# Braille_V1.net
KiCad netlist of a schematic drawn in EAGLE
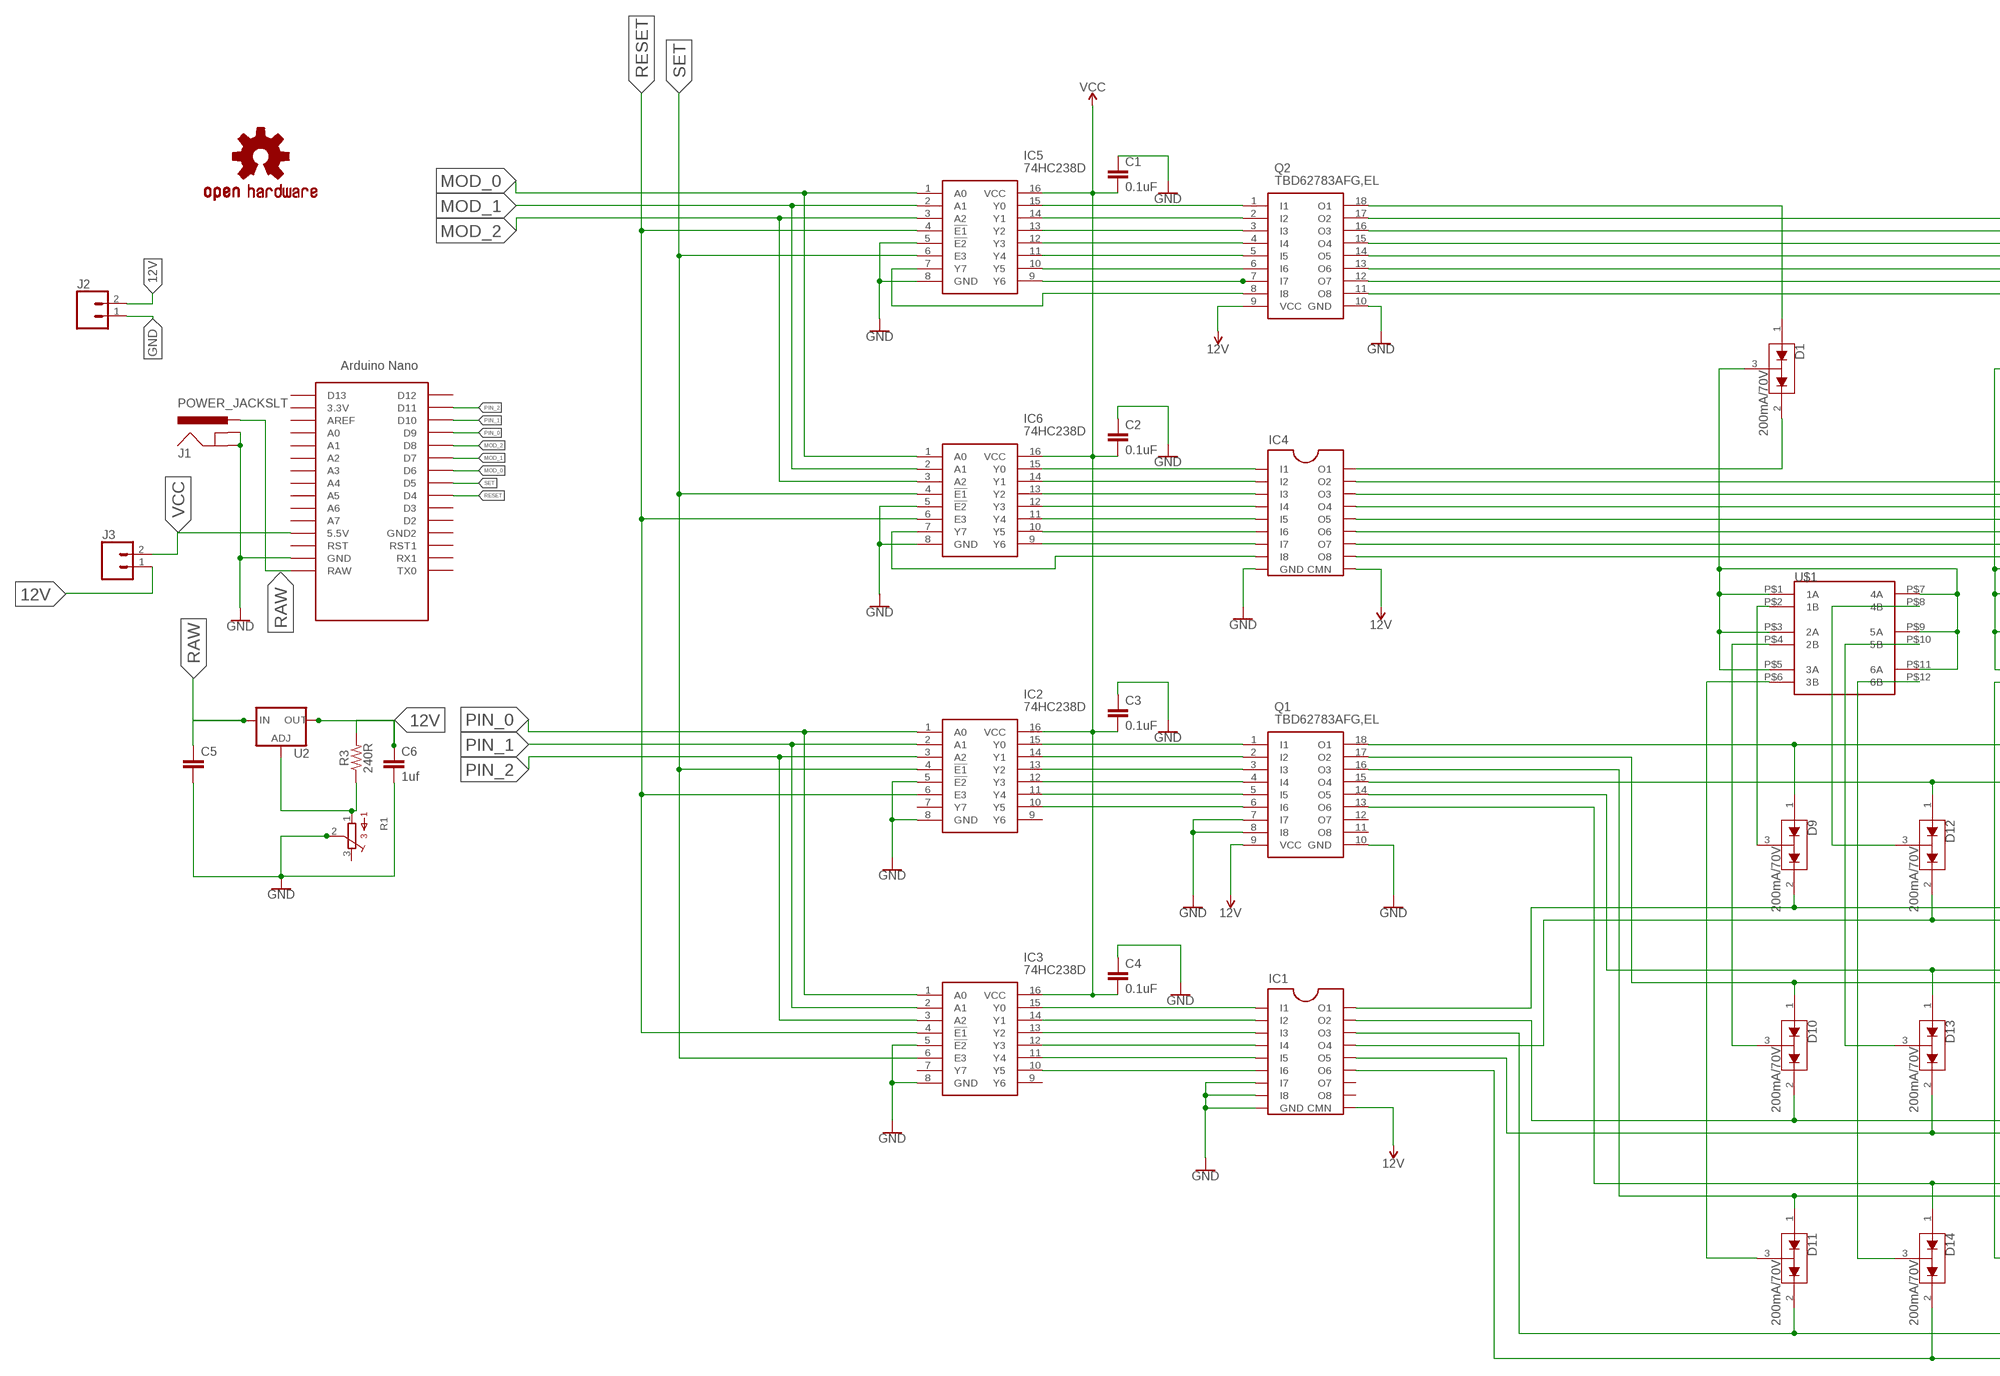
[diagram p0: schematic, sheet 1, part 1 of 2]
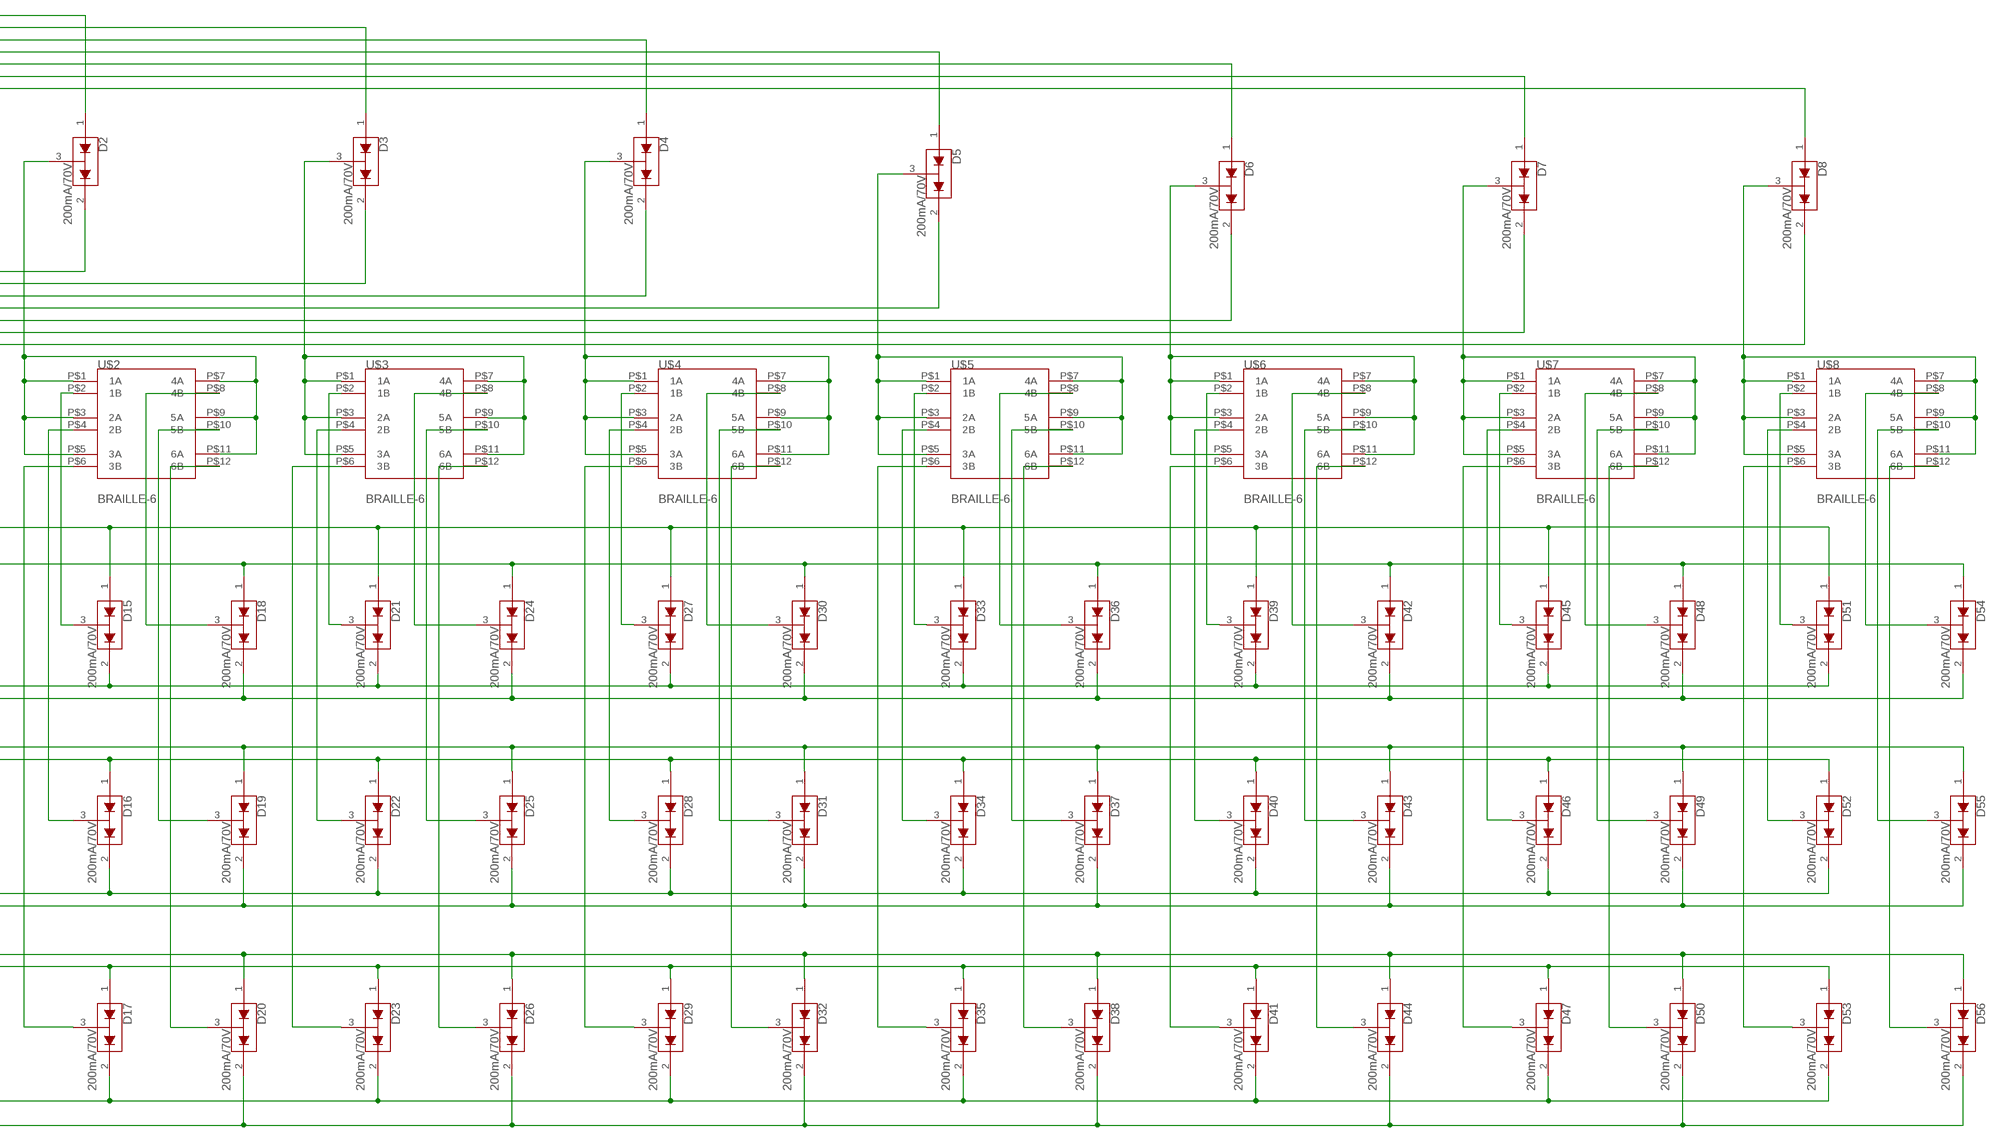
[diagram p1: schematic, sheet 1, part 2 of 2]

(export (version "E")
  (design (tool "Eeschema 10.0.6"))
  (components
    (comp (ref "C1")
      (value "0.1uF")
      (footprint "eagle-import:0603")
      (libsource (lib "eagle-import") (part "0.1UF-0603-25V-(+80/-20%)"))
    )
    (comp (ref "C2")
      (value "0.1uF")
      (footprint "eagle-import:0603")
      (libsource (lib "eagle-import") (part "0.1UF-0603-25V-(+80/-20%)"))
    )
    (comp (ref "C3")
      (value "0.1uF")
      (footprint "eagle-import:0603")
      (libsource (lib "eagle-import") (part "0.1UF-0603-25V-(+80/-20%)"))
    )
    (comp (ref "C4")
      (value "0.1uF")
      (footprint "eagle-import:0603")
      (libsource (lib "eagle-import") (part "0.1UF-0603-25V-(+80/-20%)"))
    )
    (comp (ref "C5")
      (value "0.1uF")
      (footprint "eagle-import:0603")
      (libsource (lib "eagle-import") (part "9.0PF-0603-50V-10%"))
    )
    (comp (ref "C6")
      (value "1uf")
      (footprint "eagle-import:0603")
      (libsource (lib "eagle-import") (part "9.0PF-0603-50V-10%"))
    )
    (comp (ref "D1")
      (value "200mA/70V")
      (footprint "eagle-import:SOT23-3")
      (libsource (lib "eagle-import") (part "BAV99"))
    )
    (comp (ref "D2")
      (value "200mA/70V")
      (footprint "eagle-import:SOT23-3")
      (libsource (lib "eagle-import") (part "BAV99"))
    )
    (comp (ref "D3")
      (value "200mA/70V")
      (footprint "eagle-import:SOT23-3")
      (libsource (lib "eagle-import") (part "BAV99"))
    )
    (comp (ref "D4")
      (value "200mA/70V")
      (footprint "eagle-import:SOT23-3")
      (libsource (lib "eagle-import") (part "BAV99"))
    )
    (comp (ref "D5")
      (value "200mA/70V")
      (footprint "eagle-import:SOT23-3")
      (libsource (lib "eagle-import") (part "BAV99"))
    )
    (comp (ref "D6")
      (value "200mA/70V")
      (footprint "eagle-import:SOT23-3")
      (libsource (lib "eagle-import") (part "BAV99"))
    )
    (comp (ref "D7")
      (value "200mA/70V")
      (footprint "eagle-import:SOT23-3")
      (libsource (lib "eagle-import") (part "BAV99"))
    )
    (comp (ref "D8")
      (value "200mA/70V")
      (footprint "eagle-import:SOT23-3")
      (libsource (lib "eagle-import") (part "BAV99"))
    )
    (comp (ref "D9")
      (value "200mA/70V")
      (footprint "eagle-import:SOT23-3")
      (libsource (lib "eagle-import") (part "BAV99"))
    )
    (comp (ref "D10")
      (value "200mA/70V")
      (footprint "eagle-import:SOT23-3")
      (libsource (lib "eagle-import") (part "BAV99"))
    )
    (comp (ref "D11")
      (value "200mA/70V")
      (footprint "eagle-import:SOT23-3")
      (libsource (lib "eagle-import") (part "BAV99"))
    )
    (comp (ref "D12")
      (value "200mA/70V")
      (footprint "eagle-import:SOT23-3")
      (libsource (lib "eagle-import") (part "BAV99"))
    )
    (comp (ref "D13")
      (value "200mA/70V")
      (footprint "eagle-import:SOT23-3")
      (libsource (lib "eagle-import") (part "BAV99"))
    )
    (comp (ref "D14")
      (value "200mA/70V")
      (footprint "eagle-import:SOT23-3")
      (libsource (lib "eagle-import") (part "BAV99"))
    )
    (comp (ref "D15")
      (value "200mA/70V")
      (footprint "eagle-import:SOT23-3")
      (libsource (lib "eagle-import") (part "BAV99"))
    )
    (comp (ref "D16")
      (value "200mA/70V")
      (footprint "eagle-import:SOT23-3")
      (libsource (lib "eagle-import") (part "BAV99"))
    )
    (comp (ref "D17")
      (value "200mA/70V")
      (footprint "eagle-import:SOT23-3")
      (libsource (lib "eagle-import") (part "BAV99"))
    )
    (comp (ref "D18")
      (value "200mA/70V")
      (footprint "eagle-import:SOT23-3")
      (libsource (lib "eagle-import") (part "BAV99"))
    )
    (comp (ref "D19")
      (value "200mA/70V")
      (footprint "eagle-import:SOT23-3")
      (libsource (lib "eagle-import") (part "BAV99"))
    )
    (comp (ref "D20")
      (value "200mA/70V")
      (footprint "eagle-import:SOT23-3")
      (libsource (lib "eagle-import") (part "BAV99"))
    )
    (comp (ref "D21")
      (value "200mA/70V")
      (footprint "eagle-import:SOT23-3")
      (libsource (lib "eagle-import") (part "BAV99"))
    )
    (comp (ref "D22")
      (value "200mA/70V")
      (footprint "eagle-import:SOT23-3")
      (libsource (lib "eagle-import") (part "BAV99"))
    )
    (comp (ref "D23")
      (value "200mA/70V")
      (footprint "eagle-import:SOT23-3")
      (libsource (lib "eagle-import") (part "BAV99"))
    )
    (comp (ref "D24")
      (value "200mA/70V")
      (footprint "eagle-import:SOT23-3")
      (libsource (lib "eagle-import") (part "BAV99"))
    )
    (comp (ref "D25")
      (value "200mA/70V")
      (footprint "eagle-import:SOT23-3")
      (libsource (lib "eagle-import") (part "BAV99"))
    )
    (comp (ref "D26")
      (value "200mA/70V")
      (footprint "eagle-import:SOT23-3")
      (libsource (lib "eagle-import") (part "BAV99"))
    )
    (comp (ref "D27")
      (value "200mA/70V")
      (footprint "eagle-import:SOT23-3")
      (libsource (lib "eagle-import") (part "BAV99"))
    )
    (comp (ref "D28")
      (value "200mA/70V")
      (footprint "eagle-import:SOT23-3")
      (libsource (lib "eagle-import") (part "BAV99"))
    )
    (comp (ref "D29")
      (value "200mA/70V")
      (footprint "eagle-import:SOT23-3")
      (libsource (lib "eagle-import") (part "BAV99"))
    )
    (comp (ref "D30")
      (value "200mA/70V")
      (footprint "eagle-import:SOT23-3")
      (libsource (lib "eagle-import") (part "BAV99"))
    )
    (comp (ref "D31")
      (value "200mA/70V")
      (footprint "eagle-import:SOT23-3")
      (libsource (lib "eagle-import") (part "BAV99"))
    )
    (comp (ref "D32")
      (value "200mA/70V")
      (footprint "eagle-import:SOT23-3")
      (libsource (lib "eagle-import") (part "BAV99"))
    )
    (comp (ref "D33")
      (value "200mA/70V")
      (footprint "eagle-import:SOT23-3")
      (libsource (lib "eagle-import") (part "BAV99"))
    )
    (comp (ref "D34")
      (value "200mA/70V")
      (footprint "eagle-import:SOT23-3")
      (libsource (lib "eagle-import") (part "BAV99"))
    )
    (comp (ref "D35")
      (value "200mA/70V")
      (footprint "eagle-import:SOT23-3")
      (libsource (lib "eagle-import") (part "BAV99"))
    )
    (comp (ref "D36")
      (value "200mA/70V")
      (footprint "eagle-import:SOT23-3")
      (libsource (lib "eagle-import") (part "BAV99"))
    )
    (comp (ref "D37")
      (value "200mA/70V")
      (footprint "eagle-import:SOT23-3")
      (libsource (lib "eagle-import") (part "BAV99"))
    )
    (comp (ref "D38")
      (value "200mA/70V")
      (footprint "eagle-import:SOT23-3")
      (libsource (lib "eagle-import") (part "BAV99"))
    )
    (comp (ref "D39")
      (value "200mA/70V")
      (footprint "eagle-import:SOT23-3")
      (libsource (lib "eagle-import") (part "BAV99"))
    )
    (comp (ref "D40")
      (value "200mA/70V")
      (footprint "eagle-import:SOT23-3")
      (libsource (lib "eagle-import") (part "BAV99"))
    )
    (comp (ref "D41")
      (value "200mA/70V")
      (footprint "eagle-import:SOT23-3")
      (libsource (lib "eagle-import") (part "BAV99"))
    )
    (comp (ref "D42")
      (value "200mA/70V")
      (footprint "eagle-import:SOT23-3")
      (libsource (lib "eagle-import") (part "BAV99"))
    )
    (comp (ref "D43")
      (value "200mA/70V")
      (footprint "eagle-import:SOT23-3")
      (libsource (lib "eagle-import") (part "BAV99"))
    )
    (comp (ref "D44")
      (value "200mA/70V")
      (footprint "eagle-import:SOT23-3")
      (libsource (lib "eagle-import") (part "BAV99"))
    )
    (comp (ref "D45")
      (value "200mA/70V")
      (footprint "eagle-import:SOT23-3")
      (libsource (lib "eagle-import") (part "BAV99"))
    )
    (comp (ref "D46")
      (value "200mA/70V")
      (footprint "eagle-import:SOT23-3")
      (libsource (lib "eagle-import") (part "BAV99"))
    )
    (comp (ref "D47")
      (value "200mA/70V")
      (footprint "eagle-import:SOT23-3")
      (libsource (lib "eagle-import") (part "BAV99"))
    )
    (comp (ref "D48")
      (value "200mA/70V")
      (footprint "eagle-import:SOT23-3")
      (libsource (lib "eagle-import") (part "BAV99"))
    )
    (comp (ref "D49")
      (value "200mA/70V")
      (footprint "eagle-import:SOT23-3")
      (libsource (lib "eagle-import") (part "BAV99"))
    )
    (comp (ref "D50")
      (value "200mA/70V")
      (footprint "eagle-import:SOT23-3")
      (libsource (lib "eagle-import") (part "BAV99"))
    )
    (comp (ref "D51")
      (value "200mA/70V")
      (footprint "eagle-import:SOT23-3")
      (libsource (lib "eagle-import") (part "BAV99"))
    )
    (comp (ref "D52")
      (value "200mA/70V")
      (footprint "eagle-import:SOT23-3")
      (libsource (lib "eagle-import") (part "BAV99"))
    )
    (comp (ref "D53")
      (value "200mA/70V")
      (footprint "eagle-import:SOT23-3")
      (libsource (lib "eagle-import") (part "BAV99"))
    )
    (comp (ref "D54")
      (value "200mA/70V")
      (footprint "eagle-import:SOT23-3")
      (libsource (lib "eagle-import") (part "BAV99"))
    )
    (comp (ref "D55")
      (value "200mA/70V")
      (footprint "eagle-import:SOT23-3")
      (libsource (lib "eagle-import") (part "BAV99"))
    )
    (comp (ref "D56")
      (value "200mA/70V")
      (footprint "eagle-import:SOT23-3")
      (libsource (lib "eagle-import") (part "BAV99"))
    )
    (comp (ref "IC1")
      (value "TD62083")
      (footprint "eagle-import:SO18")
      (libsource (lib "eagle-import") (part "TD62083"))
    )
    (comp (ref "IC2")
      (value "74HC238D")
      (footprint "eagle-import:SOIC127P600X175-16N")
      (fields (field (name "MOUSER_PART_NUMBER") "771-74HC238D"))
      (libsource (lib "eagle-import") (part "74HC238D"))
    )
    (comp (ref "IC3")
      (value "74HC238D")
      (footprint "eagle-import:SOIC127P600X175-16N")
      (fields (field (name "MOUSER_PART_NUMBER") "771-74HC238D"))
      (libsource (lib "eagle-import") (part "74HC238D"))
    )
    (comp (ref "IC4")
      (value "TD62083")
      (footprint "eagle-import:SO18")
      (libsource (lib "eagle-import") (part "TD62083"))
    )
    (comp (ref "IC5")
      (value "74HC238D")
      (footprint "eagle-import:SOIC127P600X175-16N")
      (fields (field (name "MOUSER_PART_NUMBER") "771-74HC238D"))
      (libsource (lib "eagle-import") (part "74HC238D"))
    )
    (comp (ref "IC6")
      (value "74HC238D")
      (footprint "eagle-import:SOIC127P600X175-16N")
      (fields (field (name "MOUSER_PART_NUMBER") "771-74HC238D"))
      (libsource (lib "eagle-import") (part "74HC238D"))
    )
    (comp (ref "J1")
      (value "POWER_JACKSLT")
      (footprint "eagle-import:POWER_JACK_SLOT")
      (libsource (lib "eagle-import") (part "POWER_JACKSLT"))
    )
    (comp (ref "J2")
      (value "CONN_02")
      (footprint "eagle-import:1X02")
      (libsource (lib "eagle-import") (part "CONN_02"))
    )
    (comp (ref "J3")
      (value "CONN_02")
      (footprint "eagle-import:1X02")
      (libsource (lib "eagle-import") (part "CONN_02"))
    )
    (comp (ref "LOGO1")
      (value "OSHW-LOGOL-COPPER")
      (footprint "eagle-import:OSHW-LOGO-L_COPPER")
      (libsource (lib "eagle-import") (part "OSHW-LOGOL-COPPER"))
    )
    (comp (ref "Q1")
      (value "TBD62783AFG,EL")
      (footprint "eagle-import:SOIC127P1030X245-18N")
      (fields (field (name "MOUSER_PART_NUMBER") "757-TBD62783AFGEL"))
      (libsource (lib "eagle-import") (part "TBD62783AFG,EL"))
    )
    (comp (ref "Q2")
      (value "TBD62783AFG,EL")
      (footprint "eagle-import:SOIC127P1030X245-18N")
      (fields (field (name "MOUSER_PART_NUMBER") "757-TBD62783AFGEL"))
      (libsource (lib "eagle-import") (part "TBD62783AFG,EL"))
    )
    (comp (ref "R1")
      (value "3362P")
      (footprint "eagle-import:3362P")
      (libsource (lib "eagle-import") (part "3362P"))
    )
    (comp (ref "R3")
      (value "240R")
      (footprint "eagle-import:0603")
      (libsource (lib "eagle-import") (part "RESISTOR0603"))
    )
    (comp (ref "U$1")
      (value "BRAILLE-6")
      (footprint "eagle-import:BRAILLE-6")
      (libsource (lib "eagle-import") (part "BRAILLE-6"))
    )
    (comp (ref "U$2")
      (value "BRAILLE-6")
      (footprint "eagle-import:BRAILLE-6")
      (libsource (lib "eagle-import") (part "BRAILLE-6"))
    )
    (comp (ref "U$3")
      (value "BRAILLE-6")
      (footprint "eagle-import:BRAILLE-6")
      (libsource (lib "eagle-import") (part "BRAILLE-6"))
    )
    (comp (ref "U$4")
      (value "BRAILLE-6")
      (footprint "eagle-import:BRAILLE-6")
      (libsource (lib "eagle-import") (part "BRAILLE-6"))
    )
    (comp (ref "U$5")
      (value "BRAILLE-6")
      (footprint "eagle-import:BRAILLE-6")
      (libsource (lib "eagle-import") (part "BRAILLE-6"))
    )
    (comp (ref "U$6")
      (value "BRAILLE-6")
      (footprint "eagle-import:BRAILLE-6")
      (libsource (lib "eagle-import") (part "BRAILLE-6"))
    )
    (comp (ref "U$7")
      (value "BRAILLE-6")
      (footprint "eagle-import:BRAILLE-6")
      (libsource (lib "eagle-import") (part "BRAILLE-6"))
    )
    (comp (ref "U$8")
      (value "BRAILLE-6")
      (footprint "eagle-import:BRAILLE-6")
      (libsource (lib "eagle-import") (part "BRAILLE-6"))
    )
    (comp (ref "U$9")
      (value "NANO")
      (footprint "eagle-import:NANO")
      (libsource (lib "eagle-import") (part "NANO"))
    )
    (comp (ref "U2")
      (value "LM317")
      (footprint "eagle-import:SOT223")
      (libsource (lib "eagle-import") (part "V_REG_317SMD"))
    )
  )
  (nets
    (net (code "1") (name "12V") (class "Default")
      (node (ref "C6") (pin "1") (pinfunction "1_1") (pintype "passive"))
      (node (ref "IC1") (pin "10") (pinfunction "CMN_10") (pintype "passive"))
      (node (ref "IC4") (pin "10") (pinfunction "CMN_10") (pintype "passive"))
      (node (ref "J2") (pin "2") (pinfunction "2_2") (pintype "passive"))
      (node (ref "J3") (pin "1") (pinfunction "1_1") (pintype "passive"))
      (node (ref "Q1") (pin "9") (pinfunction "VCC_9") (pintype "power_in"))
      (node (ref "Q2") (pin "9") (pinfunction "VCC_9") (pintype "power_in"))
      (node (ref "R3") (pin "2") (pinfunction "2_2") (pintype "passive"))
      (node (ref "U2") (pin "2") (pinfunction "OUT_2") (pintype "output"))
    )
    (net (code "2") (name "GND") (class "Default")
      (node (ref "C1") (pin "1") (pinfunction "1_1") (pintype "passive"))
      (node (ref "C2") (pin "1") (pinfunction "1_1") (pintype "passive"))
      (node (ref "C3") (pin "1") (pinfunction "1_1") (pintype "passive"))
      (node (ref "C4") (pin "1") (pinfunction "1_1") (pintype "passive"))
      (node (ref "C5") (pin "2") (pinfunction "2_2") (pintype "passive"))
      (node (ref "C6") (pin "2") (pinfunction "2_2") (pintype "passive"))
      (node (ref "IC1") (pin "7") (pinfunction "I7_7") (pintype "passive"))
      (node (ref "IC1") (pin "8") (pinfunction "I8_8") (pintype "passive"))
      (node (ref "IC1") (pin "9") (pinfunction "GND_9") (pintype "passive"))
      (node (ref "IC2") (pin "5") (pinfunction "~{E2}_5") (pintype "bidirectional"))
      (node (ref "IC2") (pin "8") (pinfunction "GND_8") (pintype "bidirectional"))
      (node (ref "IC3") (pin "5") (pinfunction "~{E2}_5") (pintype "bidirectional"))
      (node (ref "IC3") (pin "8") (pinfunction "GND_8") (pintype "bidirectional"))
      (node (ref "IC4") (pin "9") (pinfunction "GND_9") (pintype "passive"))
      (node (ref "IC5") (pin "5") (pinfunction "~{E2}_5") (pintype "bidirectional"))
      (node (ref "IC5") (pin "8") (pinfunction "GND_8") (pintype "bidirectional"))
      (node (ref "IC6") (pin "5") (pinfunction "~{E2}_5") (pintype "bidirectional"))
      (node (ref "IC6") (pin "8") (pinfunction "GND_8") (pintype "bidirectional"))
      (node (ref "J1") (pin "GND@1") (pinfunction "GNDBREAK_GND@1") (pintype "bidirectional"))
      (node (ref "J1") (pin "GND@2") (pinfunction "GND_GND@2") (pintype "bidirectional"))
      (node (ref "J2") (pin "1") (pinfunction "1_1") (pintype "passive"))
      (node (ref "Q1") (pin "10") (pinfunction "GND_10") (pintype "power_in"))
      (node (ref "Q1") (pin "7") (pinfunction "I7_7") (pintype "input"))
      (node (ref "Q1") (pin "8") (pinfunction "I8_8") (pintype "input"))
      (node (ref "Q2") (pin "10") (pinfunction "GND_10") (pintype "power_in"))
      (node (ref "R1") (pin "2") (pinfunction "2_2") (pintype "passive"))
      (node (ref "U$9") (pin "GND") (pinfunction "GND_GND") (pintype "bidirectional"))
    )
    (net (code "3") (name "MOD_0") (class "Default")
      (node (ref "IC5") (pin "1") (pinfunction "A0_1") (pintype "bidirectional"))
      (node (ref "IC6") (pin "1") (pinfunction "A0_1") (pintype "bidirectional"))
      (node (ref "U$9") (pin "D6") (pinfunction "D6_D6") (pintype "bidirectional"))
    )
    (net (code "4") (name "MOD_1") (class "Default")
      (node (ref "IC5") (pin "2") (pinfunction "A1_2") (pintype "bidirectional"))
      (node (ref "IC6") (pin "2") (pinfunction "A1_2") (pintype "bidirectional"))
      (node (ref "U$9") (pin "D7") (pinfunction "D7_D7") (pintype "bidirectional"))
    )
    (net (code "5") (name "MOD_2") (class "Default")
      (node (ref "IC5") (pin "3") (pinfunction "A2_3") (pintype "bidirectional"))
      (node (ref "IC6") (pin "3") (pinfunction "A2_3") (pintype "bidirectional"))
      (node (ref "U$9") (pin "D8") (pinfunction "D8_D8") (pintype "bidirectional"))
    )
    (net (code "6") (name "Net-(D1-A1)") (class "Default")
      (node (ref "D1") (pin "1") (pinfunction "A1_1") (pintype "bidirectional"))
      (node (ref "Q2") (pin "18") (pinfunction "O1_18") (pintype "output"))
    )
    (net (code "7") (name "Net-(D1-C2)") (class "Default")
      (node (ref "D1") (pin "2") (pinfunction "C2_2") (pintype "bidirectional"))
      (node (ref "IC4") (pin "18") (pinfunction "O1_18") (pintype "passive"))
    )
    (net (code "8") (name "Net-(D1-COM)") (class "Default")
      (node (ref "D1") (pin "3") (pinfunction "COM_3") (pintype "bidirectional"))
      (node (ref "U$1") (pin "P$1") (pinfunction "1A_P$1") (pintype "bidirectional"))
      (node (ref "U$1") (pin "P$11") (pinfunction "6A_P$11") (pintype "bidirectional"))
      (node (ref "U$1") (pin "P$3") (pinfunction "2A_P$3") (pintype "bidirectional"))
      (node (ref "U$1") (pin "P$5") (pinfunction "3A_P$5") (pintype "bidirectional"))
      (node (ref "U$1") (pin "P$7") (pinfunction "4A_P$7") (pintype "bidirectional"))
      (node (ref "U$1") (pin "P$9") (pinfunction "5A_P$9") (pintype "bidirectional"))
    )
    (net (code "9") (name "Net-(D2-A1)") (class "Default")
      (node (ref "D2") (pin "1") (pinfunction "A1_1") (pintype "bidirectional"))
      (node (ref "Q2") (pin "17") (pinfunction "O2_17") (pintype "output"))
    )
    (net (code "10") (name "Net-(D2-C2)") (class "Default")
      (node (ref "D2") (pin "2") (pinfunction "C2_2") (pintype "bidirectional"))
      (node (ref "IC4") (pin "17") (pinfunction "O2_17") (pintype "passive"))
    )
    (net (code "11") (name "Net-(D2-COM)") (class "Default")
      (node (ref "D2") (pin "3") (pinfunction "COM_3") (pintype "bidirectional"))
      (node (ref "U$2") (pin "P$1") (pinfunction "1A_P$1") (pintype "bidirectional"))
      (node (ref "U$2") (pin "P$11") (pinfunction "6A_P$11") (pintype "bidirectional"))
      (node (ref "U$2") (pin "P$3") (pinfunction "2A_P$3") (pintype "bidirectional"))
      (node (ref "U$2") (pin "P$5") (pinfunction "3A_P$5") (pintype "bidirectional"))
      (node (ref "U$2") (pin "P$7") (pinfunction "4A_P$7") (pintype "bidirectional"))
      (node (ref "U$2") (pin "P$9") (pinfunction "5A_P$9") (pintype "bidirectional"))
    )
    (net (code "12") (name "Net-(D3-A1)") (class "Default")
      (node (ref "D3") (pin "1") (pinfunction "A1_1") (pintype "bidirectional"))
      (node (ref "Q2") (pin "16") (pinfunction "O3_16") (pintype "output"))
    )
    (net (code "13") (name "Net-(D3-C2)") (class "Default")
      (node (ref "D3") (pin "2") (pinfunction "C2_2") (pintype "bidirectional"))
      (node (ref "IC4") (pin "16") (pinfunction "O3_16") (pintype "passive"))
    )
    (net (code "14") (name "Net-(D3-COM)") (class "Default")
      (node (ref "D3") (pin "3") (pinfunction "COM_3") (pintype "bidirectional"))
      (node (ref "U$3") (pin "P$1") (pinfunction "1A_P$1") (pintype "bidirectional"))
      (node (ref "U$3") (pin "P$11") (pinfunction "6A_P$11") (pintype "bidirectional"))
      (node (ref "U$3") (pin "P$3") (pinfunction "2A_P$3") (pintype "bidirectional"))
      (node (ref "U$3") (pin "P$5") (pinfunction "3A_P$5") (pintype "bidirectional"))
      (node (ref "U$3") (pin "P$7") (pinfunction "4A_P$7") (pintype "bidirectional"))
      (node (ref "U$3") (pin "P$9") (pinfunction "5A_P$9") (pintype "bidirectional"))
    )
    (net (code "15") (name "Net-(D4-A1)") (class "Default")
      (node (ref "D4") (pin "1") (pinfunction "A1_1") (pintype "bidirectional"))
      (node (ref "Q2") (pin "15") (pinfunction "O4_15") (pintype "output"))
    )
    (net (code "16") (name "Net-(D4-C2)") (class "Default")
      (node (ref "D4") (pin "2") (pinfunction "C2_2") (pintype "bidirectional"))
      (node (ref "IC4") (pin "15") (pinfunction "O4_15") (pintype "passive"))
    )
    (net (code "17") (name "Net-(D4-COM)") (class "Default")
      (node (ref "D4") (pin "3") (pinfunction "COM_3") (pintype "bidirectional"))
      (node (ref "U$4") (pin "P$1") (pinfunction "1A_P$1") (pintype "bidirectional"))
      (node (ref "U$4") (pin "P$11") (pinfunction "6A_P$11") (pintype "bidirectional"))
      (node (ref "U$4") (pin "P$3") (pinfunction "2A_P$3") (pintype "bidirectional"))
      (node (ref "U$4") (pin "P$5") (pinfunction "3A_P$5") (pintype "bidirectional"))
      (node (ref "U$4") (pin "P$7") (pinfunction "4A_P$7") (pintype "bidirectional"))
      (node (ref "U$4") (pin "P$9") (pinfunction "5A_P$9") (pintype "bidirectional"))
    )
    (net (code "18") (name "Net-(D5-A1)") (class "Default")
      (node (ref "D5") (pin "1") (pinfunction "A1_1") (pintype "bidirectional"))
      (node (ref "Q2") (pin "14") (pinfunction "O5_14") (pintype "output"))
    )
    (net (code "19") (name "Net-(D5-C2)") (class "Default")
      (node (ref "D5") (pin "2") (pinfunction "C2_2") (pintype "bidirectional"))
      (node (ref "IC4") (pin "14") (pinfunction "O5_14") (pintype "passive"))
    )
    (net (code "20") (name "Net-(D5-COM)") (class "Default")
      (node (ref "D5") (pin "3") (pinfunction "COM_3") (pintype "bidirectional"))
      (node (ref "U$5") (pin "P$1") (pinfunction "1A_P$1") (pintype "bidirectional"))
      (node (ref "U$5") (pin "P$11") (pinfunction "6A_P$11") (pintype "bidirectional"))
      (node (ref "U$5") (pin "P$3") (pinfunction "2A_P$3") (pintype "bidirectional"))
      (node (ref "U$5") (pin "P$5") (pinfunction "3A_P$5") (pintype "bidirectional"))
      (node (ref "U$5") (pin "P$7") (pinfunction "4A_P$7") (pintype "bidirectional"))
      (node (ref "U$5") (pin "P$9") (pinfunction "5A_P$9") (pintype "bidirectional"))
    )
    (net (code "21") (name "Net-(D6-A1)") (class "Default")
      (node (ref "D6") (pin "1") (pinfunction "A1_1") (pintype "bidirectional"))
      (node (ref "Q2") (pin "13") (pinfunction "O6_13") (pintype "output"))
    )
    (net (code "22") (name "Net-(D6-C2)") (class "Default")
      (node (ref "D6") (pin "2") (pinfunction "C2_2") (pintype "bidirectional"))
      (node (ref "IC4") (pin "13") (pinfunction "O6_13") (pintype "passive"))
    )
    (net (code "23") (name "Net-(D6-COM)") (class "Default")
      (node (ref "D6") (pin "3") (pinfunction "COM_3") (pintype "bidirectional"))
      (node (ref "U$6") (pin "P$1") (pinfunction "1A_P$1") (pintype "bidirectional"))
      (node (ref "U$6") (pin "P$11") (pinfunction "6A_P$11") (pintype "bidirectional"))
      (node (ref "U$6") (pin "P$3") (pinfunction "2A_P$3") (pintype "bidirectional"))
      (node (ref "U$6") (pin "P$5") (pinfunction "3A_P$5") (pintype "bidirectional"))
      (node (ref "U$6") (pin "P$7") (pinfunction "4A_P$7") (pintype "bidirectional"))
      (node (ref "U$6") (pin "P$9") (pinfunction "5A_P$9") (pintype "bidirectional"))
    )
    (net (code "24") (name "Net-(D7-A1)") (class "Default")
      (node (ref "D7") (pin "1") (pinfunction "A1_1") (pintype "bidirectional"))
      (node (ref "Q2") (pin "12") (pinfunction "O7_12") (pintype "output"))
    )
    (net (code "25") (name "Net-(D7-C2)") (class "Default")
      (node (ref "D7") (pin "2") (pinfunction "C2_2") (pintype "bidirectional"))
      (node (ref "IC4") (pin "12") (pinfunction "O7_12") (pintype "passive"))
    )
    (net (code "26") (name "Net-(D7-COM)") (class "Default")
      (node (ref "D7") (pin "3") (pinfunction "COM_3") (pintype "bidirectional"))
      (node (ref "U$7") (pin "P$1") (pinfunction "1A_P$1") (pintype "bidirectional"))
      (node (ref "U$7") (pin "P$11") (pinfunction "6A_P$11") (pintype "bidirectional"))
      (node (ref "U$7") (pin "P$3") (pinfunction "2A_P$3") (pintype "bidirectional"))
      (node (ref "U$7") (pin "P$5") (pinfunction "3A_P$5") (pintype "bidirectional"))
      (node (ref "U$7") (pin "P$7") (pinfunction "4A_P$7") (pintype "bidirectional"))
      (node (ref "U$7") (pin "P$9") (pinfunction "5A_P$9") (pintype "bidirectional"))
    )
    (net (code "27") (name "Net-(D8-A1)") (class "Default")
      (node (ref "D8") (pin "1") (pinfunction "A1_1") (pintype "bidirectional"))
      (node (ref "Q2") (pin "11") (pinfunction "O8_11") (pintype "output"))
    )
    (net (code "28") (name "Net-(D8-C2)") (class "Default")
      (node (ref "D8") (pin "2") (pinfunction "C2_2") (pintype "bidirectional"))
      (node (ref "IC4") (pin "11") (pinfunction "O8_11") (pintype "passive"))
    )
    (net (code "29") (name "Net-(D8-COM)") (class "Default")
      (node (ref "D8") (pin "3") (pinfunction "COM_3") (pintype "bidirectional"))
      (node (ref "U$8") (pin "P$1") (pinfunction "1A_P$1") (pintype "bidirectional"))
      (node (ref "U$8") (pin "P$11") (pinfunction "6A_P$11") (pintype "bidirectional"))
      (node (ref "U$8") (pin "P$3") (pinfunction "2A_P$3") (pintype "bidirectional"))
      (node (ref "U$8") (pin "P$5") (pinfunction "3A_P$5") (pintype "bidirectional"))
      (node (ref "U$8") (pin "P$7") (pinfunction "4A_P$7") (pintype "bidirectional"))
      (node (ref "U$8") (pin "P$9") (pinfunction "5A_P$9") (pintype "bidirectional"))
    )
    (net (code "30") (name "Net-(D9-COM)") (class "Default")
      (node (ref "D9") (pin "3") (pinfunction "COM_3") (pintype "bidirectional"))
      (node (ref "U$1") (pin "P$2") (pinfunction "1B_P$2") (pintype "bidirectional"))
    )
    (net (code "31") (name "Net-(D10-A1)") (class "Default")
      (node (ref "D10") (pin "1") (pinfunction "A1_1") (pintype "bidirectional"))
      (node (ref "D16") (pin "1") (pinfunction "A1_1") (pintype "bidirectional"))
      (node (ref "D22") (pin "1") (pinfunction "A1_1") (pintype "bidirectional"))
      (node (ref "D28") (pin "1") (pinfunction "A1_1") (pintype "bidirectional"))
      (node (ref "D34") (pin "1") (pinfunction "A1_1") (pintype "bidirectional"))
      (node (ref "D40") (pin "1") (pinfunction "A1_1") (pintype "bidirectional"))
      (node (ref "D46") (pin "1") (pinfunction "A1_1") (pintype "bidirectional"))
      (node (ref "D52") (pin "1") (pinfunction "A1_1") (pintype "bidirectional"))
      (node (ref "Q1") (pin "17") (pinfunction "O2_17") (pintype "output"))
    )
    (net (code "32") (name "Net-(D10-C2)") (class "Default")
      (node (ref "D10") (pin "2") (pinfunction "C2_2") (pintype "bidirectional"))
      (node (ref "D16") (pin "2") (pinfunction "C2_2") (pintype "bidirectional"))
      (node (ref "D22") (pin "2") (pinfunction "C2_2") (pintype "bidirectional"))
      (node (ref "D28") (pin "2") (pinfunction "C2_2") (pintype "bidirectional"))
      (node (ref "D34") (pin "2") (pinfunction "C2_2") (pintype "bidirectional"))
      (node (ref "D40") (pin "2") (pinfunction "C2_2") (pintype "bidirectional"))
      (node (ref "D46") (pin "2") (pinfunction "C2_2") (pintype "bidirectional"))
      (node (ref "D52") (pin "2") (pinfunction "C2_2") (pintype "bidirectional"))
      (node (ref "IC1") (pin "17") (pinfunction "O2_17") (pintype "passive"))
    )
    (net (code "33") (name "Net-(D10-COM)") (class "Default")
      (node (ref "D10") (pin "3") (pinfunction "COM_3") (pintype "bidirectional"))
      (node (ref "U$1") (pin "P$4") (pinfunction "2B_P$4") (pintype "bidirectional"))
    )
    (net (code "34") (name "Net-(D11-A1)") (class "Default")
      (node (ref "D11") (pin "1") (pinfunction "A1_1") (pintype "bidirectional"))
      (node (ref "D17") (pin "1") (pinfunction "A1_1") (pintype "bidirectional"))
      (node (ref "D23") (pin "1") (pinfunction "A1_1") (pintype "bidirectional"))
      (node (ref "D29") (pin "1") (pinfunction "A1_1") (pintype "bidirectional"))
      (node (ref "D35") (pin "1") (pinfunction "A1_1") (pintype "bidirectional"))
      (node (ref "D41") (pin "1") (pinfunction "A1_1") (pintype "bidirectional"))
      (node (ref "D47") (pin "1") (pinfunction "A1_1") (pintype "bidirectional"))
      (node (ref "D53") (pin "1") (pinfunction "A1_1") (pintype "bidirectional"))
      (node (ref "Q1") (pin "16") (pinfunction "O3_16") (pintype "output"))
    )
    (net (code "35") (name "Net-(D11-C2)") (class "Default")
      (node (ref "D11") (pin "2") (pinfunction "C2_2") (pintype "bidirectional"))
      (node (ref "D17") (pin "2") (pinfunction "C2_2") (pintype "bidirectional"))
      (node (ref "D23") (pin "2") (pinfunction "C2_2") (pintype "bidirectional"))
      (node (ref "D29") (pin "2") (pinfunction "C2_2") (pintype "bidirectional"))
      (node (ref "D35") (pin "2") (pinfunction "C2_2") (pintype "bidirectional"))
      (node (ref "D41") (pin "2") (pinfunction "C2_2") (pintype "bidirectional"))
      (node (ref "D47") (pin "2") (pinfunction "C2_2") (pintype "bidirectional"))
      (node (ref "D53") (pin "2") (pinfunction "C2_2") (pintype "bidirectional"))
      (node (ref "IC1") (pin "16") (pinfunction "O3_16") (pintype "passive"))
    )
    (net (code "36") (name "Net-(D11-COM)") (class "Default")
      (node (ref "D11") (pin "3") (pinfunction "COM_3") (pintype "bidirectional"))
      (node (ref "U$1") (pin "P$6") (pinfunction "3B_P$6") (pintype "bidirectional"))
    )
    (net (code "37") (name "Net-(D12-A1)") (class "Default")
      (node (ref "D12") (pin "1") (pinfunction "A1_1") (pintype "bidirectional"))
      (node (ref "D18") (pin "1") (pinfunction "A1_1") (pintype "bidirectional"))
      (node (ref "D24") (pin "1") (pinfunction "A1_1") (pintype "bidirectional"))
      (node (ref "D30") (pin "1") (pinfunction "A1_1") (pintype "bidirectional"))
      (node (ref "D36") (pin "1") (pinfunction "A1_1") (pintype "bidirectional"))
      (node (ref "D42") (pin "1") (pinfunction "A1_1") (pintype "bidirectional"))
      (node (ref "D48") (pin "1") (pinfunction "A1_1") (pintype "bidirectional"))
      (node (ref "D54") (pin "1") (pinfunction "A1_1") (pintype "bidirectional"))
      (node (ref "Q1") (pin "15") (pinfunction "O4_15") (pintype "output"))
    )
    (net (code "38") (name "Net-(D12-C2)") (class "Default")
      (node (ref "D12") (pin "2") (pinfunction "C2_2") (pintype "bidirectional"))
      (node (ref "D18") (pin "2") (pinfunction "C2_2") (pintype "bidirectional"))
      (node (ref "D24") (pin "2") (pinfunction "C2_2") (pintype "bidirectional"))
      (node (ref "D30") (pin "2") (pinfunction "C2_2") (pintype "bidirectional"))
      (node (ref "D36") (pin "2") (pinfunction "C2_2") (pintype "bidirectional"))
      (node (ref "D42") (pin "2") (pinfunction "C2_2") (pintype "bidirectional"))
      (node (ref "D48") (pin "2") (pinfunction "C2_2") (pintype "bidirectional"))
      (node (ref "D54") (pin "2") (pinfunction "C2_2") (pintype "bidirectional"))
      (node (ref "IC1") (pin "15") (pinfunction "O4_15") (pintype "passive"))
    )
    (net (code "39") (name "Net-(D12-COM)") (class "Default")
      (node (ref "D12") (pin "3") (pinfunction "COM_3") (pintype "bidirectional"))
      (node (ref "U$1") (pin "P$8") (pinfunction "4B_P$8") (pintype "bidirectional"))
    )
    (net (code "40") (name "Net-(D13-A1)") (class "Default")
      (node (ref "D13") (pin "1") (pinfunction "A1_1") (pintype "bidirectional"))
      (node (ref "D19") (pin "1") (pinfunction "A1_1") (pintype "bidirectional"))
      (node (ref "D25") (pin "1") (pinfunction "A1_1") (pintype "bidirectional"))
      (node (ref "D31") (pin "1") (pinfunction "A1_1") (pintype "bidirectional"))
      (node (ref "D37") (pin "1") (pinfunction "A1_1") (pintype "bidirectional"))
      (node (ref "D43") (pin "1") (pinfunction "A1_1") (pintype "bidirectional"))
      (node (ref "D49") (pin "1") (pinfunction "A1_1") (pintype "bidirectional"))
      (node (ref "D55") (pin "1") (pinfunction "A1_1") (pintype "bidirectional"))
      (node (ref "Q1") (pin "14") (pinfunction "O5_14") (pintype "output"))
    )
    (net (code "41") (name "Net-(D13-C2)") (class "Default")
      (node (ref "D13") (pin "2") (pinfunction "C2_2") (pintype "bidirectional"))
      (node (ref "D19") (pin "2") (pinfunction "C2_2") (pintype "bidirectional"))
      (node (ref "D25") (pin "2") (pinfunction "C2_2") (pintype "bidirectional"))
      (node (ref "D31") (pin "2") (pinfunction "C2_2") (pintype "bidirectional"))
      (node (ref "D37") (pin "2") (pinfunction "C2_2") (pintype "bidirectional"))
      (node (ref "D43") (pin "2") (pinfunction "C2_2") (pintype "bidirectional"))
      (node (ref "D49") (pin "2") (pinfunction "C2_2") (pintype "bidirectional"))
      (node (ref "D55") (pin "2") (pinfunction "C2_2") (pintype "bidirectional"))
      (node (ref "IC1") (pin "14") (pinfunction "O5_14") (pintype "passive"))
    )
    (net (code "42") (name "Net-(D13-COM)") (class "Default")
      (node (ref "D13") (pin "3") (pinfunction "COM_3") (pintype "bidirectional"))
      (node (ref "U$1") (pin "P$10") (pinfunction "5B_P$10") (pintype "bidirectional"))
    )
    (net (code "43") (name "Net-(D14-A1)") (class "Default")
      (node (ref "D14") (pin "1") (pinfunction "A1_1") (pintype "bidirectional"))
      (node (ref "D20") (pin "1") (pinfunction "A1_1") (pintype "bidirectional"))
      (node (ref "D26") (pin "1") (pinfunction "A1_1") (pintype "bidirectional"))
      (node (ref "D32") (pin "1") (pinfunction "A1_1") (pintype "bidirectional"))
      (node (ref "D38") (pin "1") (pinfunction "A1_1") (pintype "bidirectional"))
      (node (ref "D44") (pin "1") (pinfunction "A1_1") (pintype "bidirectional"))
      (node (ref "D50") (pin "1") (pinfunction "A1_1") (pintype "bidirectional"))
      (node (ref "D56") (pin "1") (pinfunction "A1_1") (pintype "bidirectional"))
      (node (ref "Q1") (pin "13") (pinfunction "O6_13") (pintype "output"))
    )
    (net (code "44") (name "Net-(D14-C2)") (class "Default")
      (node (ref "D14") (pin "2") (pinfunction "C2_2") (pintype "bidirectional"))
      (node (ref "D20") (pin "2") (pinfunction "C2_2") (pintype "bidirectional"))
      (node (ref "D26") (pin "2") (pinfunction "C2_2") (pintype "bidirectional"))
      (node (ref "D32") (pin "2") (pinfunction "C2_2") (pintype "bidirectional"))
      (node (ref "D38") (pin "2") (pinfunction "C2_2") (pintype "bidirectional"))
      (node (ref "D44") (pin "2") (pinfunction "C2_2") (pintype "bidirectional"))
      (node (ref "D50") (pin "2") (pinfunction "C2_2") (pintype "bidirectional"))
      (node (ref "D56") (pin "2") (pinfunction "C2_2") (pintype "bidirectional"))
      (node (ref "IC1") (pin "13") (pinfunction "O6_13") (pintype "passive"))
    )
    (net (code "45") (name "Net-(D14-COM)") (class "Default")
      (node (ref "D14") (pin "3") (pinfunction "COM_3") (pintype "bidirectional"))
      (node (ref "U$1") (pin "P$12") (pinfunction "6B_P$12") (pintype "bidirectional"))
    )
    (net (code "46") (name "Net-(D15-A1)") (class "Default")
      (node (ref "D15") (pin "1") (pinfunction "A1_1") (pintype "bidirectional"))
      (node (ref "D21") (pin "1") (pinfunction "A1_1") (pintype "bidirectional"))
      (node (ref "D27") (pin "1") (pinfunction "A1_1") (pintype "bidirectional"))
      (node (ref "D33") (pin "1") (pinfunction "A1_1") (pintype "bidirectional"))
      (node (ref "D39") (pin "1") (pinfunction "A1_1") (pintype "bidirectional"))
      (node (ref "D45") (pin "1") (pinfunction "A1_1") (pintype "bidirectional"))
      (node (ref "D51") (pin "1") (pinfunction "A1_1") (pintype "bidirectional"))
      (node (ref "D9") (pin "1") (pinfunction "A1_1") (pintype "bidirectional"))
      (node (ref "Q1") (pin "18") (pinfunction "O1_18") (pintype "output"))
    )
    (net (code "47") (name "Net-(D15-C2)") (class "Default")
      (node (ref "D15") (pin "2") (pinfunction "C2_2") (pintype "bidirectional"))
      (node (ref "D21") (pin "2") (pinfunction "C2_2") (pintype "bidirectional"))
      (node (ref "D27") (pin "2") (pinfunction "C2_2") (pintype "bidirectional"))
      (node (ref "D33") (pin "2") (pinfunction "C2_2") (pintype "bidirectional"))
      (node (ref "D39") (pin "2") (pinfunction "C2_2") (pintype "bidirectional"))
      (node (ref "D45") (pin "2") (pinfunction "C2_2") (pintype "bidirectional"))
      (node (ref "D51") (pin "2") (pinfunction "C2_2") (pintype "bidirectional"))
      (node (ref "D9") (pin "2") (pinfunction "C2_2") (pintype "bidirectional"))
      (node (ref "IC1") (pin "18") (pinfunction "O1_18") (pintype "passive"))
    )
    (net (code "48") (name "Net-(D15-COM)") (class "Default")
      (node (ref "D15") (pin "3") (pinfunction "COM_3") (pintype "bidirectional"))
      (node (ref "U$2") (pin "P$2") (pinfunction "1B_P$2") (pintype "bidirectional"))
    )
    (net (code "49") (name "Net-(D16-COM)") (class "Default")
      (node (ref "D16") (pin "3") (pinfunction "COM_3") (pintype "bidirectional"))
      (node (ref "U$2") (pin "P$4") (pinfunction "2B_P$4") (pintype "bidirectional"))
    )
    (net (code "50") (name "Net-(D17-COM)") (class "Default")
      (node (ref "D17") (pin "3") (pinfunction "COM_3") (pintype "bidirectional"))
      (node (ref "U$2") (pin "P$6") (pinfunction "3B_P$6") (pintype "bidirectional"))
    )
    (net (code "51") (name "Net-(D18-COM)") (class "Default")
      (node (ref "D18") (pin "3") (pinfunction "COM_3") (pintype "bidirectional"))
      (node (ref "U$2") (pin "P$8") (pinfunction "4B_P$8") (pintype "bidirectional"))
    )
    (net (code "52") (name "Net-(D19-COM)") (class "Default")
      (node (ref "D19") (pin "3") (pinfunction "COM_3") (pintype "bidirectional"))
      (node (ref "U$2") (pin "P$10") (pinfunction "5B_P$10") (pintype "bidirectional"))
    )
    (net (code "53") (name "Net-(D20-COM)") (class "Default")
      (node (ref "D20") (pin "3") (pinfunction "COM_3") (pintype "bidirectional"))
      (node (ref "U$2") (pin "P$12") (pinfunction "6B_P$12") (pintype "bidirectional"))
    )
    (net (code "54") (name "Net-(D21-COM)") (class "Default")
      (node (ref "D21") (pin "3") (pinfunction "COM_3") (pintype "bidirectional"))
      (node (ref "U$3") (pin "P$2") (pinfunction "1B_P$2") (pintype "bidirectional"))
    )
    (net (code "55") (name "Net-(D22-COM)") (class "Default")
      (node (ref "D22") (pin "3") (pinfunction "COM_3") (pintype "bidirectional"))
      (node (ref "U$3") (pin "P$4") (pinfunction "2B_P$4") (pintype "bidirectional"))
    )
    (net (code "56") (name "Net-(D23-COM)") (class "Default")
      (node (ref "D23") (pin "3") (pinfunction "COM_3") (pintype "bidirectional"))
      (node (ref "U$3") (pin "P$6") (pinfunction "3B_P$6") (pintype "bidirectional"))
    )
    (net (code "57") (name "Net-(D24-COM)") (class "Default")
      (node (ref "D24") (pin "3") (pinfunction "COM_3") (pintype "bidirectional"))
      (node (ref "U$3") (pin "P$8") (pinfunction "4B_P$8") (pintype "bidirectional"))
    )
    (net (code "58") (name "Net-(D25-COM)") (class "Default")
      (node (ref "D25") (pin "3") (pinfunction "COM_3") (pintype "bidirectional"))
      (node (ref "U$3") (pin "P$10") (pinfunction "5B_P$10") (pintype "bidirectional"))
    )
    (net (code "59") (name "Net-(D26-COM)") (class "Default")
      (node (ref "D26") (pin "3") (pinfunction "COM_3") (pintype "bidirectional"))
      (node (ref "U$3") (pin "P$12") (pinfunction "6B_P$12") (pintype "bidirectional"))
    )
    (net (code "60") (name "Net-(D27-COM)") (class "Default")
      (node (ref "D27") (pin "3") (pinfunction "COM_3") (pintype "bidirectional"))
      (node (ref "U$4") (pin "P$2") (pinfunction "1B_P$2") (pintype "bidirectional"))
    )
    (net (code "61") (name "Net-(D28-COM)") (class "Default")
      (node (ref "D28") (pin "3") (pinfunction "COM_3") (pintype "bidirectional"))
      (node (ref "U$4") (pin "P$4") (pinfunction "2B_P$4") (pintype "bidirectional"))
    )
    (net (code "62") (name "Net-(D29-COM)") (class "Default")
      (node (ref "D29") (pin "3") (pinfunction "COM_3") (pintype "bidirectional"))
      (node (ref "U$4") (pin "P$6") (pinfunction "3B_P$6") (pintype "bidirectional"))
    )
    (net (code "63") (name "Net-(D30-COM)") (class "Default")
      (node (ref "D30") (pin "3") (pinfunction "COM_3") (pintype "bidirectional"))
      (node (ref "U$4") (pin "P$8") (pinfunction "4B_P$8") (pintype "bidirectional"))
    )
    (net (code "64") (name "Net-(D31-COM)") (class "Default")
      (node (ref "D31") (pin "3") (pinfunction "COM_3") (pintype "bidirectional"))
      (node (ref "U$4") (pin "P$10") (pinfunction "5B_P$10") (pintype "bidirectional"))
    )
    (net (code "65") (name "Net-(D32-COM)") (class "Default")
      (node (ref "D32") (pin "3") (pinfunction "COM_3") (pintype "bidirectional"))
      (node (ref "U$4") (pin "P$12") (pinfunction "6B_P$12") (pintype "bidirectional"))
    )
    (net (code "66") (name "Net-(D33-COM)") (class "Default")
      (node (ref "D33") (pin "3") (pinfunction "COM_3") (pintype "bidirectional"))
      (node (ref "U$5") (pin "P$2") (pinfunction "1B_P$2") (pintype "bidirectional"))
    )
    (net (code "67") (name "Net-(D34-COM)") (class "Default")
      (node (ref "D34") (pin "3") (pinfunction "COM_3") (pintype "bidirectional"))
      (node (ref "U$5") (pin "P$4") (pinfunction "2B_P$4") (pintype "bidirectional"))
    )
    (net (code "68") (name "Net-(D35-COM)") (class "Default")
      (node (ref "D35") (pin "3") (pinfunction "COM_3") (pintype "bidirectional"))
      (node (ref "U$5") (pin "P$6") (pinfunction "3B_P$6") (pintype "bidirectional"))
    )
    (net (code "69") (name "Net-(D36-COM)") (class "Default")
      (node (ref "D36") (pin "3") (pinfunction "COM_3") (pintype "bidirectional"))
      (node (ref "U$5") (pin "P$8") (pinfunction "4B_P$8") (pintype "bidirectional"))
    )
    (net (code "70") (name "Net-(D37-COM)") (class "Default")
      (node (ref "D37") (pin "3") (pinfunction "COM_3") (pintype "bidirectional"))
      (node (ref "U$5") (pin "P$10") (pinfunction "5B_P$10") (pintype "bidirectional"))
    )
    (net (code "71") (name "Net-(D38-COM)") (class "Default")
      (node (ref "D38") (pin "3") (pinfunction "COM_3") (pintype "bidirectional"))
      (node (ref "U$5") (pin "P$12") (pinfunction "6B_P$12") (pintype "bidirectional"))
    )
    (net (code "72") (name "Net-(D39-COM)") (class "Default")
      (node (ref "D39") (pin "3") (pinfunction "COM_3") (pintype "bidirectional"))
      (node (ref "U$6") (pin "P$2") (pinfunction "1B_P$2") (pintype "bidirectional"))
    )
    (net (code "73") (name "Net-(D40-COM)") (class "Default")
      (node (ref "D40") (pin "3") (pinfunction "COM_3") (pintype "bidirectional"))
      (node (ref "U$6") (pin "P$4") (pinfunction "2B_P$4") (pintype "bidirectional"))
    )
    (net (code "74") (name "Net-(D41-COM)") (class "Default")
      (node (ref "D41") (pin "3") (pinfunction "COM_3") (pintype "bidirectional"))
      (node (ref "U$6") (pin "P$6") (pinfunction "3B_P$6") (pintype "bidirectional"))
    )
    (net (code "75") (name "Net-(D42-COM)") (class "Default")
      (node (ref "D42") (pin "3") (pinfunction "COM_3") (pintype "bidirectional"))
      (node (ref "U$6") (pin "P$8") (pinfunction "4B_P$8") (pintype "bidirectional"))
    )
    (net (code "76") (name "Net-(D43-COM)") (class "Default")
      (node (ref "D43") (pin "3") (pinfunction "COM_3") (pintype "bidirectional"))
      (node (ref "U$6") (pin "P$10") (pinfunction "5B_P$10") (pintype "bidirectional"))
    )
    (net (code "77") (name "Net-(D44-COM)") (class "Default")
      (node (ref "D44") (pin "3") (pinfunction "COM_3") (pintype "bidirectional"))
      (node (ref "U$6") (pin "P$12") (pinfunction "6B_P$12") (pintype "bidirectional"))
    )
    (net (code "78") (name "Net-(D45-COM)") (class "Default")
      (node (ref "D45") (pin "3") (pinfunction "COM_3") (pintype "bidirectional"))
      (node (ref "U$7") (pin "P$2") (pinfunction "1B_P$2") (pintype "bidirectional"))
    )
    (net (code "79") (name "Net-(D46-COM)") (class "Default")
      (node (ref "D46") (pin "3") (pinfunction "COM_3") (pintype "bidirectional"))
      (node (ref "U$7") (pin "P$4") (pinfunction "2B_P$4") (pintype "bidirectional"))
    )
    (net (code "80") (name "Net-(D47-COM)") (class "Default")
      (node (ref "D47") (pin "3") (pinfunction "COM_3") (pintype "bidirectional"))
      (node (ref "U$7") (pin "P$6") (pinfunction "3B_P$6") (pintype "bidirectional"))
    )
    (net (code "81") (name "Net-(D48-COM)") (class "Default")
      (node (ref "D48") (pin "3") (pinfunction "COM_3") (pintype "bidirectional"))
      (node (ref "U$7") (pin "P$8") (pinfunction "4B_P$8") (pintype "bidirectional"))
    )
    (net (code "82") (name "Net-(D49-COM)") (class "Default")
      (node (ref "D49") (pin "3") (pinfunction "COM_3") (pintype "bidirectional"))
      (node (ref "U$7") (pin "P$10") (pinfunction "5B_P$10") (pintype "bidirectional"))
    )
    (net (code "83") (name "Net-(D50-COM)") (class "Default")
      (node (ref "D50") (pin "3") (pinfunction "COM_3") (pintype "bidirectional"))
      (node (ref "U$7") (pin "P$12") (pinfunction "6B_P$12") (pintype "bidirectional"))
    )
    (net (code "84") (name "Net-(D51-COM)") (class "Default")
      (node (ref "D51") (pin "3") (pinfunction "COM_3") (pintype "bidirectional"))
      (node (ref "U$8") (pin "P$2") (pinfunction "1B_P$2") (pintype "bidirectional"))
    )
    (net (code "85") (name "Net-(D52-COM)") (class "Default")
      (node (ref "D52") (pin "3") (pinfunction "COM_3") (pintype "bidirectional"))
      (node (ref "U$8") (pin "P$4") (pinfunction "2B_P$4") (pintype "bidirectional"))
    )
    (net (code "86") (name "Net-(D53-COM)") (class "Default")
      (node (ref "D53") (pin "3") (pinfunction "COM_3") (pintype "bidirectional"))
      (node (ref "U$8") (pin "P$6") (pinfunction "3B_P$6") (pintype "bidirectional"))
    )
    (net (code "87") (name "Net-(D54-COM)") (class "Default")
      (node (ref "D54") (pin "3") (pinfunction "COM_3") (pintype "bidirectional"))
      (node (ref "U$8") (pin "P$8") (pinfunction "4B_P$8") (pintype "bidirectional"))
    )
    (net (code "88") (name "Net-(D55-COM)") (class "Default")
      (node (ref "D55") (pin "3") (pinfunction "COM_3") (pintype "bidirectional"))
      (node (ref "U$8") (pin "P$10") (pinfunction "5B_P$10") (pintype "bidirectional"))
    )
    (net (code "89") (name "Net-(D56-COM)") (class "Default")
      (node (ref "D56") (pin "3") (pinfunction "COM_3") (pintype "bidirectional"))
      (node (ref "U$8") (pin "P$12") (pinfunction "6B_P$12") (pintype "bidirectional"))
    )
    (net (code "90") (name "Net-(IC1-I1)") (class "Default")
      (node (ref "IC1") (pin "1") (pinfunction "I1_1") (pintype "passive"))
      (node (ref "IC3") (pin "15") (pinfunction "Y0_15") (pintype "bidirectional"))
    )
    (net (code "91") (name "Net-(IC1-I2)") (class "Default")
      (node (ref "IC1") (pin "2") (pinfunction "I2_2") (pintype "passive"))
      (node (ref "IC3") (pin "14") (pinfunction "Y1_14") (pintype "bidirectional"))
    )
    (net (code "92") (name "Net-(IC1-I3)") (class "Default")
      (node (ref "IC1") (pin "3") (pinfunction "I3_3") (pintype "passive"))
      (node (ref "IC3") (pin "13") (pinfunction "Y2_13") (pintype "bidirectional"))
    )
    (net (code "93") (name "Net-(IC1-I4)") (class "Default")
      (node (ref "IC1") (pin "4") (pinfunction "I4_4") (pintype "passive"))
      (node (ref "IC3") (pin "12") (pinfunction "Y3_12") (pintype "bidirectional"))
    )
    (net (code "94") (name "Net-(IC1-I5)") (class "Default")
      (node (ref "IC1") (pin "5") (pinfunction "I5_5") (pintype "passive"))
      (node (ref "IC3") (pin "11") (pinfunction "Y4_11") (pintype "bidirectional"))
    )
    (net (code "95") (name "Net-(IC1-I6)") (class "Default")
      (node (ref "IC1") (pin "6") (pinfunction "I6_6") (pintype "passive"))
      (node (ref "IC3") (pin "10") (pinfunction "Y5_10") (pintype "bidirectional"))
    )
    (net (code "96") (name "Net-(IC2-Y0)") (class "Default")
      (node (ref "IC2") (pin "15") (pinfunction "Y0_15") (pintype "bidirectional"))
      (node (ref "Q1") (pin "1") (pinfunction "I1_1") (pintype "input"))
    )
    (net (code "97") (name "Net-(IC2-Y1)") (class "Default")
      (node (ref "IC2") (pin "14") (pinfunction "Y1_14") (pintype "bidirectional"))
      (node (ref "Q1") (pin "2") (pinfunction "I2_2") (pintype "input"))
    )
    (net (code "98") (name "Net-(IC2-Y2)") (class "Default")
      (node (ref "IC2") (pin "13") (pinfunction "Y2_13") (pintype "bidirectional"))
      (node (ref "Q1") (pin "3") (pinfunction "I3_3") (pintype "input"))
    )
    (net (code "99") (name "Net-(IC2-Y3)") (class "Default")
      (node (ref "IC2") (pin "12") (pinfunction "Y3_12") (pintype "bidirectional"))
      (node (ref "Q1") (pin "4") (pinfunction "I4_4") (pintype "input"))
    )
    (net (code "100") (name "Net-(IC2-Y4)") (class "Default")
      (node (ref "IC2") (pin "11") (pinfunction "Y4_11") (pintype "bidirectional"))
      (node (ref "Q1") (pin "5") (pinfunction "I5_5") (pintype "input"))
    )
    (net (code "101") (name "Net-(IC2-Y5)") (class "Default")
      (node (ref "IC2") (pin "10") (pinfunction "Y5_10") (pintype "bidirectional"))
      (node (ref "Q1") (pin "6") (pinfunction "I6_6") (pintype "input"))
    )
    (net (code "102") (name "Net-(IC4-I1)") (class "Default")
      (node (ref "IC4") (pin "1") (pinfunction "I1_1") (pintype "passive"))
      (node (ref "IC6") (pin "15") (pinfunction "Y0_15") (pintype "bidirectional"))
    )
    (net (code "103") (name "Net-(IC4-I2)") (class "Default")
      (node (ref "IC4") (pin "2") (pinfunction "I2_2") (pintype "passive"))
      (node (ref "IC6") (pin "14") (pinfunction "Y1_14") (pintype "bidirectional"))
    )
    (net (code "104") (name "Net-(IC4-I3)") (class "Default")
      (node (ref "IC4") (pin "3") (pinfunction "I3_3") (pintype "passive"))
      (node (ref "IC6") (pin "13") (pinfunction "Y2_13") (pintype "bidirectional"))
    )
    (net (code "105") (name "Net-(IC4-I4)") (class "Default")
      (node (ref "IC4") (pin "4") (pinfunction "I4_4") (pintype "passive"))
      (node (ref "IC6") (pin "12") (pinfunction "Y3_12") (pintype "bidirectional"))
    )
    (net (code "106") (name "Net-(IC4-I5)") (class "Default")
      (node (ref "IC4") (pin "5") (pinfunction "I5_5") (pintype "passive"))
      (node (ref "IC6") (pin "11") (pinfunction "Y4_11") (pintype "bidirectional"))
    )
    (net (code "107") (name "Net-(IC4-I6)") (class "Default")
      (node (ref "IC4") (pin "6") (pinfunction "I6_6") (pintype "passive"))
      (node (ref "IC6") (pin "10") (pinfunction "Y5_10") (pintype "bidirectional"))
    )
    (net (code "108") (name "Net-(IC4-I7)") (class "Default")
      (node (ref "IC4") (pin "7") (pinfunction "I7_7") (pintype "passive"))
      (node (ref "IC6") (pin "9") (pinfunction "Y6_9") (pintype "bidirectional"))
    )
    (net (code "109") (name "Net-(IC4-I8)") (class "Default")
      (node (ref "IC4") (pin "8") (pinfunction "I8_8") (pintype "passive"))
      (node (ref "IC6") (pin "7") (pinfunction "Y7_7") (pintype "bidirectional"))
    )
    (net (code "110") (name "Net-(IC5-Y0)") (class "Default")
      (node (ref "IC5") (pin "15") (pinfunction "Y0_15") (pintype "bidirectional"))
      (node (ref "Q2") (pin "1") (pinfunction "I1_1") (pintype "input"))
    )
    (net (code "111") (name "Net-(IC5-Y1)") (class "Default")
      (node (ref "IC5") (pin "14") (pinfunction "Y1_14") (pintype "bidirectional"))
      (node (ref "Q2") (pin "2") (pinfunction "I2_2") (pintype "input"))
    )
    (net (code "112") (name "Net-(IC5-Y2)") (class "Default")
      (node (ref "IC5") (pin "13") (pinfunction "Y2_13") (pintype "bidirectional"))
      (node (ref "Q2") (pin "3") (pinfunction "I3_3") (pintype "input"))
    )
    (net (code "113") (name "Net-(IC5-Y3)") (class "Default")
      (node (ref "IC5") (pin "12") (pinfunction "Y3_12") (pintype "bidirectional"))
      (node (ref "Q2") (pin "4") (pinfunction "I4_4") (pintype "input"))
    )
    (net (code "114") (name "Net-(IC5-Y4)") (class "Default")
      (node (ref "IC5") (pin "11") (pinfunction "Y4_11") (pintype "bidirectional"))
      (node (ref "Q2") (pin "5") (pinfunction "I5_5") (pintype "input"))
    )
    (net (code "115") (name "Net-(IC5-Y5)") (class "Default")
      (node (ref "IC5") (pin "10") (pinfunction "Y5_10") (pintype "bidirectional"))
      (node (ref "Q2") (pin "6") (pinfunction "I6_6") (pintype "input"))
    )
    (net (code "116") (name "Net-(IC5-Y6)") (class "Default")
      (node (ref "IC5") (pin "9") (pinfunction "Y6_9") (pintype "bidirectional"))
      (node (ref "Q2") (pin "7") (pinfunction "I7_7") (pintype "input"))
    )
    (net (code "117") (name "Net-(IC5-Y7)") (class "Default")
      (node (ref "IC5") (pin "7") (pinfunction "Y7_7") (pintype "bidirectional"))
      (node (ref "Q2") (pin "8") (pinfunction "I8_8") (pintype "input"))
    )
    (net (code "118") (name "Net-(U2-ADJ)") (class "Default")
      (node (ref "R1") (pin "1") (pinfunction "1_1") (pintype "passive"))
      (node (ref "R3") (pin "1") (pinfunction "1_1") (pintype "passive"))
      (node (ref "U2") (pin "1") (pinfunction "ADJ_1") (pintype "input"))
    )
    (net (code "119") (name "PIN_0") (class "Default")
      (node (ref "IC2") (pin "1") (pinfunction "A0_1") (pintype "bidirectional"))
      (node (ref "IC3") (pin "1") (pinfunction "A0_1") (pintype "bidirectional"))
      (node (ref "U$9") (pin "D9") (pinfunction "D9_D9") (pintype "bidirectional"))
    )
    (net (code "120") (name "PIN_1") (class "Default")
      (node (ref "IC2") (pin "2") (pinfunction "A1_2") (pintype "bidirectional"))
      (node (ref "IC3") (pin "2") (pinfunction "A1_2") (pintype "bidirectional"))
      (node (ref "U$9") (pin "D10") (pinfunction "D10_D10") (pintype "bidirectional"))
    )
    (net (code "121") (name "PIN_2") (class "Default")
      (node (ref "IC2") (pin "3") (pinfunction "A2_3") (pintype "bidirectional"))
      (node (ref "IC3") (pin "3") (pinfunction "A2_3") (pintype "bidirectional"))
      (node (ref "U$9") (pin "D11") (pinfunction "D11_D11") (pintype "bidirectional"))
    )
    (net (code "122") (name "RAW") (class "Default")
      (node (ref "C5") (pin "1") (pinfunction "1_1") (pintype "passive"))
      (node (ref "J1") (pin "PWR") (pinfunction "PWR_PWR") (pintype "bidirectional"))
      (node (ref "U$9") (pin "RAW") (pinfunction "RAW_RAW") (pintype "bidirectional"))
      (node (ref "U2") (pin "3") (pinfunction "IN_3") (pintype "input"))
    )
    (net (code "123") (name "RESET") (class "Default")
      (node (ref "IC2") (pin "6") (pinfunction "E3_6") (pintype "bidirectional"))
      (node (ref "IC3") (pin "4") (pinfunction "~{E1}_4") (pintype "bidirectional"))
      (node (ref "IC5") (pin "4") (pinfunction "~{E1}_4") (pintype "bidirectional"))
      (node (ref "IC6") (pin "6") (pinfunction "E3_6") (pintype "bidirectional"))
      (node (ref "U$9") (pin "D4") (pinfunction "D4_D4") (pintype "bidirectional"))
    )
    (net (code "124") (name "SET") (class "Default")
      (node (ref "IC2") (pin "4") (pinfunction "~{E1}_4") (pintype "bidirectional"))
      (node (ref "IC3") (pin "6") (pinfunction "E3_6") (pintype "bidirectional"))
      (node (ref "IC5") (pin "6") (pinfunction "E3_6") (pintype "bidirectional"))
      (node (ref "IC6") (pin "4") (pinfunction "~{E1}_4") (pintype "bidirectional"))
      (node (ref "U$9") (pin "D5") (pinfunction "D5_D5") (pintype "bidirectional"))
    )
    (net (code "125") (name "VCC") (class "Default")
      (node (ref "C1") (pin "2") (pinfunction "2_2") (pintype "passive"))
      (node (ref "C2") (pin "2") (pinfunction "2_2") (pintype "passive"))
      (node (ref "C3") (pin "2") (pinfunction "2_2") (pintype "passive"))
      (node (ref "C4") (pin "2") (pinfunction "2_2") (pintype "passive"))
      (node (ref "IC2") (pin "16") (pinfunction "VCC_16") (pintype "bidirectional"))
      (node (ref "IC3") (pin "16") (pinfunction "VCC_16") (pintype "bidirectional"))
      (node (ref "IC5") (pin "16") (pinfunction "VCC_16") (pintype "bidirectional"))
      (node (ref "IC6") (pin "16") (pinfunction "VCC_16") (pintype "bidirectional"))
      (node (ref "J3") (pin "2") (pinfunction "2_2") (pintype "passive"))
      (node (ref "U$9") (pin "5V") (pinfunction "5.5V_5V") (pintype "bidirectional"))
    )
    (net (code "126") (name "unconnected-(IC1-O7-Pad12)") (class "Default")
      (node (ref "IC1") (pin "12") (pinfunction "O7_12") (pintype "passive"))
    )
    (net (code "127") (name "unconnected-(IC1-O8-Pad11)") (class "Default")
      (node (ref "IC1") (pin "11") (pinfunction "O8_11") (pintype "passive"))
    )
    (net (code "128") (name "unconnected-(IC2-Y6-Pad9)") (class "Default")
      (node (ref "IC2") (pin "9") (pinfunction "Y6_9") (pintype "bidirectional"))
    )
    (net (code "129") (name "unconnected-(IC2-Y7-Pad7)") (class "Default")
      (node (ref "IC2") (pin "7") (pinfunction "Y7_7") (pintype "bidirectional"))
    )
    (net (code "130") (name "unconnected-(IC3-Y6-Pad9)") (class "Default")
      (node (ref "IC3") (pin "9") (pinfunction "Y6_9") (pintype "bidirectional"))
    )
    (net (code "131") (name "unconnected-(IC3-Y7-Pad7)") (class "Default")
      (node (ref "IC3") (pin "7") (pinfunction "Y7_7") (pintype "bidirectional"))
    )
    (net (code "132") (name "unconnected-(Q1-O7-Pad12)") (class "Default")
      (node (ref "Q1") (pin "12") (pinfunction "O7_12") (pintype "output"))
    )
    (net (code "133") (name "unconnected-(Q1-O8-Pad11)") (class "Default")
      (node (ref "Q1") (pin "11") (pinfunction "O8_11") (pintype "output"))
    )
    (net (code "134") (name "unconnected-(R1-Pad3)") (class "Default")
      (node (ref "R1") (pin "3") (pinfunction "3_3") (pintype "passive"))
    )
    (net (code "135") (name "unconnected-(U$9-GND2-PadGND1)") (class "Default")
      (node (ref "U$9") (pin "GND1") (pinfunction "GND2_GND1") (pintype "bidirectional"))
    )
    (net (code "136") (name "unconnected-(U$9-Pad3.3V)") (class "Default")
      (node (ref "U$9") (pin "3.3V") (pinfunction "3.3V_3.3V") (pintype "bidirectional"))
    )
    (net (code "137") (name "unconnected-(U$9-PadA0)") (class "Default")
      (node (ref "U$9") (pin "A0") (pinfunction "A0_A0") (pintype "bidirectional"))
    )
    (net (code "138") (name "unconnected-(U$9-PadA1)") (class "Default")
      (node (ref "U$9") (pin "A1") (pinfunction "A1_A1") (pintype "bidirectional"))
    )
    (net (code "139") (name "unconnected-(U$9-PadA2)") (class "Default")
      (node (ref "U$9") (pin "A2") (pinfunction "A2_A2") (pintype "bidirectional"))
    )
    (net (code "140") (name "unconnected-(U$9-PadA3)") (class "Default")
      (node (ref "U$9") (pin "A3") (pinfunction "A3_A3") (pintype "bidirectional"))
    )
    (net (code "141") (name "unconnected-(U$9-PadA4)") (class "Default")
      (node (ref "U$9") (pin "A4") (pinfunction "A4_A4") (pintype "bidirectional"))
    )
    (net (code "142") (name "unconnected-(U$9-PadA5)") (class "Default")
      (node (ref "U$9") (pin "A5") (pinfunction "A5_A5") (pintype "bidirectional"))
    )
    (net (code "143") (name "unconnected-(U$9-PadA6)") (class "Default")
      (node (ref "U$9") (pin "A6") (pinfunction "A6_A6") (pintype "bidirectional"))
    )
    (net (code "144") (name "unconnected-(U$9-PadA7)") (class "Default")
      (node (ref "U$9") (pin "A7") (pinfunction "A7_A7") (pintype "bidirectional"))
    )
    (net (code "145") (name "unconnected-(U$9-PadAREF)") (class "Default")
      (node (ref "U$9") (pin "AREF") (pinfunction "AREF_AREF") (pintype "bidirectional"))
    )
    (net (code "146") (name "unconnected-(U$9-PadD2)") (class "Default")
      (node (ref "U$9") (pin "D2") (pinfunction "D2_D2") (pintype "bidirectional"))
    )
    (net (code "147") (name "unconnected-(U$9-PadD3)") (class "Default")
      (node (ref "U$9") (pin "D3") (pinfunction "D3_D3") (pintype "bidirectional"))
    )
    (net (code "148") (name "unconnected-(U$9-PadD12)") (class "Default")
      (node (ref "U$9") (pin "D12") (pinfunction "D12_D12") (pintype "bidirectional"))
    )
    (net (code "149") (name "unconnected-(U$9-PadD13)") (class "Default")
      (node (ref "U$9") (pin "D13") (pinfunction "D13_D13") (pintype "bidirectional"))
    )
    (net (code "150") (name "unconnected-(U$9-PadICSP1)") (class "Default")
      (node (ref "U$9") (pin "ICSP1") (pinfunction "ICSP1_ICSP1") (pintype "bidirectional"))
    )
    (net (code "151") (name "unconnected-(U$9-PadICSP2)") (class "Default")
      (node (ref "U$9") (pin "ICSP2") (pinfunction "ICSP2_ICSP2") (pintype "bidirectional"))
    )
    (net (code "152") (name "unconnected-(U$9-PadICSP3)") (class "Default")
      (node (ref "U$9") (pin "ICSP3") (pinfunction "ICSP3_ICSP3") (pintype "bidirectional"))
    )
    (net (code "153") (name "unconnected-(U$9-PadICSP4)") (class "Default")
      (node (ref "U$9") (pin "ICSP4") (pinfunction "ICSP4_ICSP4") (pintype "bidirectional"))
    )
    (net (code "154") (name "unconnected-(U$9-PadICSP5)") (class "Default")
      (node (ref "U$9") (pin "ICSP5") (pinfunction "ICSP5_ICSP5") (pintype "bidirectional"))
    )
    (net (code "155") (name "unconnected-(U$9-PadICSP6)") (class "Default")
      (node (ref "U$9") (pin "ICSP6") (pinfunction "ICSP6_ICSP6") (pintype "bidirectional"))
    )
    (net (code "156") (name "unconnected-(U$9-PadRST)") (class "Default")
      (node (ref "U$9") (pin "RST") (pinfunction "RST_RST") (pintype "bidirectional"))
    )
    (net (code "157") (name "unconnected-(U$9-PadRST1)") (class "Default")
      (node (ref "U$9") (pin "RST1") (pinfunction "RST1_RST1") (pintype "bidirectional"))
    )
    (net (code "158") (name "unconnected-(U$9-PadRX1)") (class "Default")
      (node (ref "U$9") (pin "RX1") (pinfunction "RX1_RX1") (pintype "bidirectional"))
    )
    (net (code "159") (name "unconnected-(U$9-PadTX0)") (class "Default")
      (node (ref "U$9") (pin "TX0") (pinfunction "TX0_TX0") (pintype "bidirectional"))
    )
  )
)
